# RadToF.net
KiCad netlist of a schematic drawn in Altium Designer
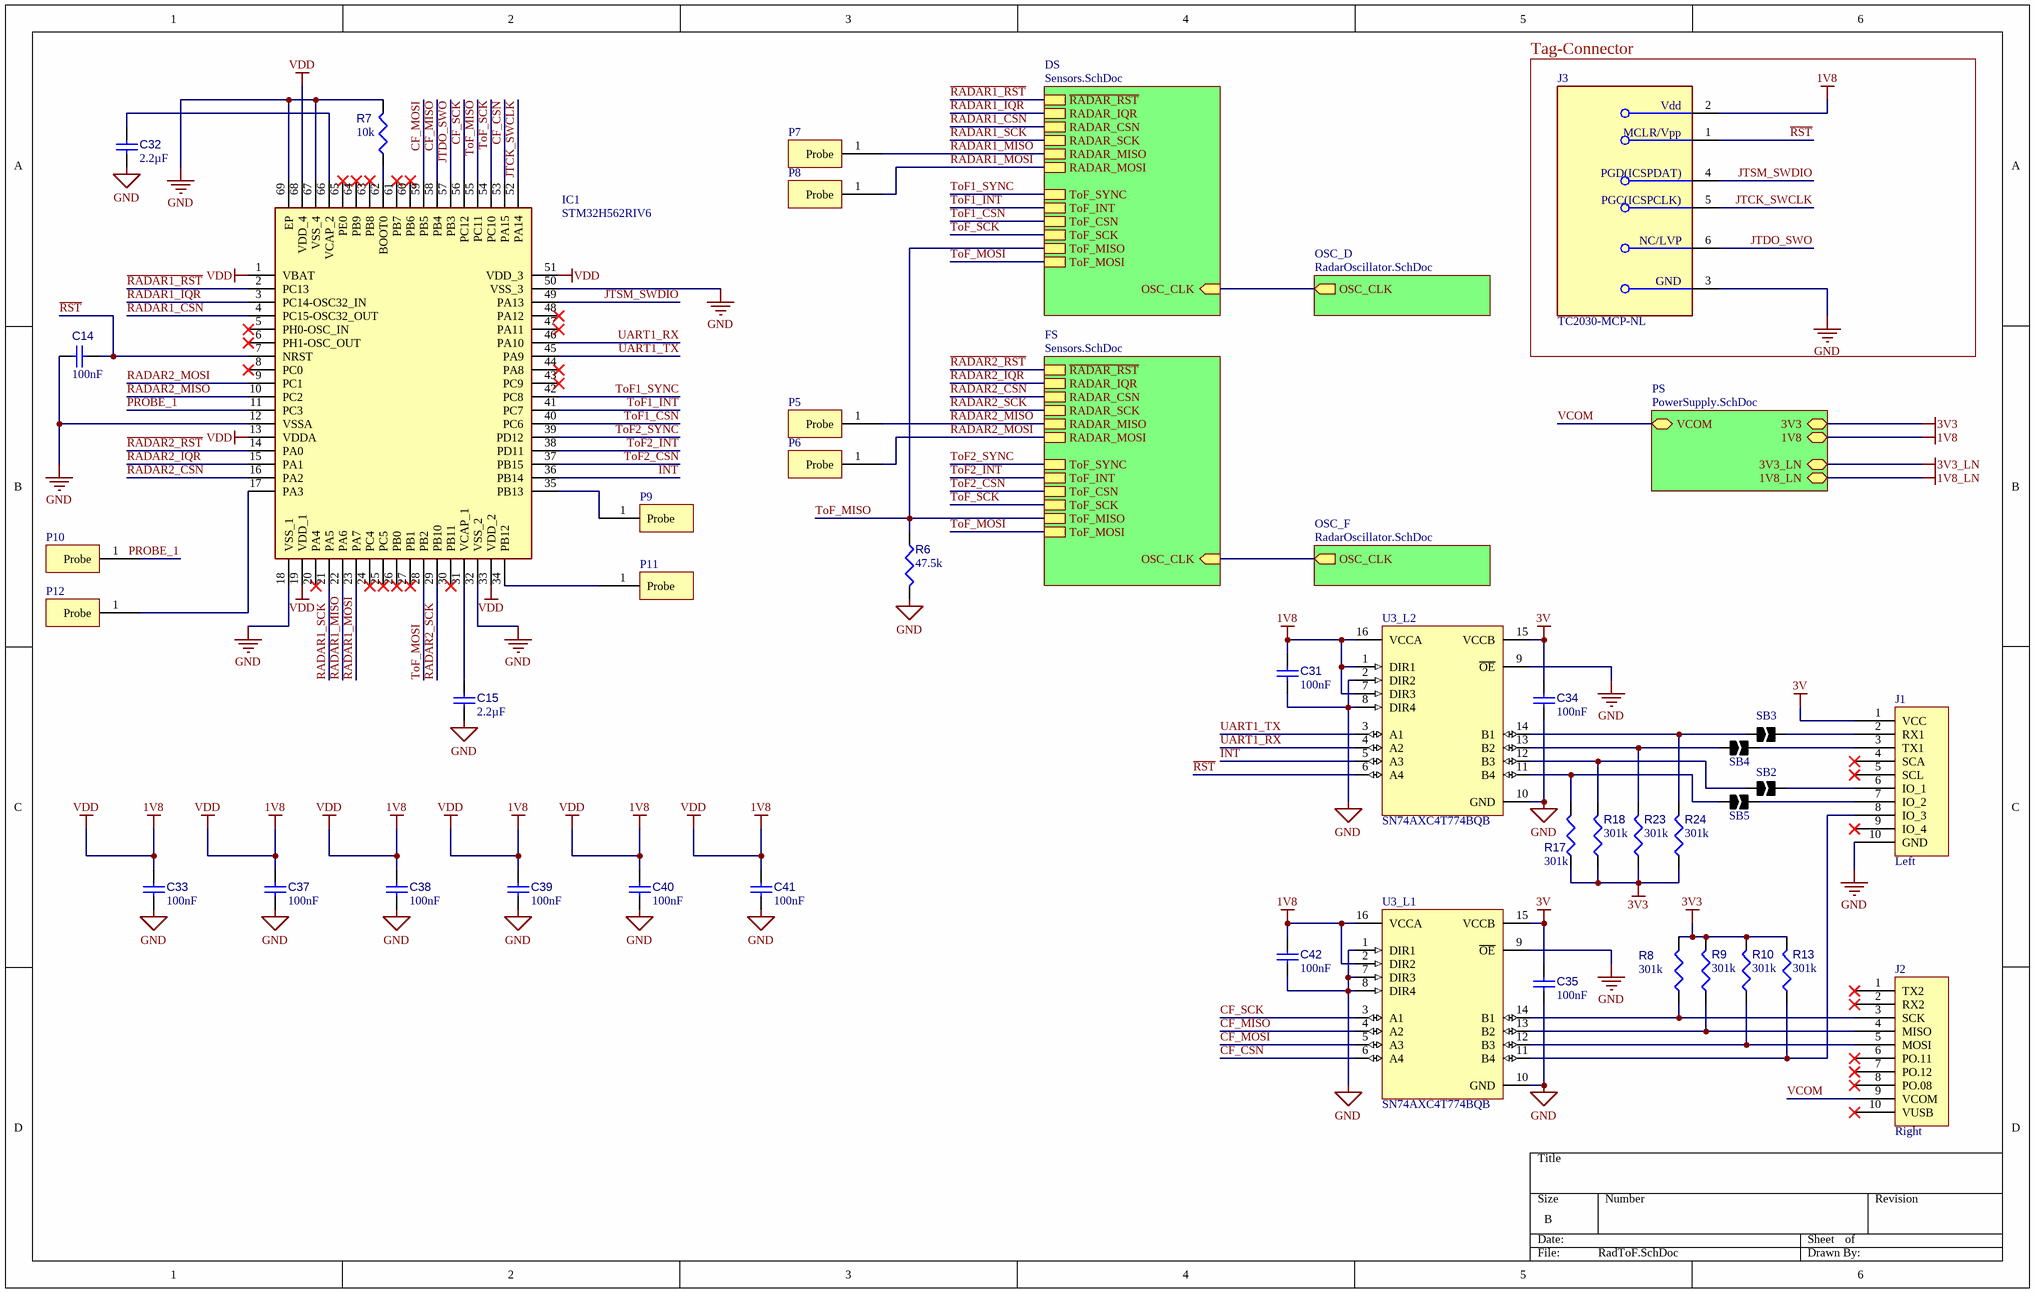
[diagram p0: RadToF.SchDoc]

(export (version "E")
  (design (tool "Eeschema 10.0.6"))
  (components
    (comp (ref "C14")
      (value "100nF")
      (footprint "CAPC0402(1005)60_L")
      (description "Chip Capacitor, 100nF +/-20%, 50V, 0402, Thickness 0.6 mm")
      (fields (field (name "TOLERANCE") "10%") (field (name "Comment") "Capacitor 100nF +/-20% 50V 0402"))
      (libsource (lib "Patrick Hupertz") (part "CAP-NP-2"))
    )
    (comp (ref "C15")
      (value "2.2µF")
      (footprint "CAPC0402(1005)60_L")
      (description "Chip Capacitor, 2,2µF +/-20%, 10V, 0402, Thickness 0.6 mm")
      (fields (field (name "TOLERANCE") "10%") (field (name "Comment") "Capacitor 2,2µF +/-20% 10V 0402"))
      (libsource (lib "Patrick Hupertz") (part "CAP-NP-2"))
    )
    (comp (ref "C31")
      (value "100nF")
      (footprint "CAPC0402(1005)60_L")
      (description "Chip Capacitor, 100nF +/-20%, 50V, 0402, Thickness 0.6 mm")
      (fields (field (name "TOLERANCE") "10%") (field (name "Comment") "Capacitor 100nF +/-20% 50V 0402"))
      (libsource (lib "Patrick Hupertz") (part "CAP-NP-2"))
    )
    (comp (ref "C32")
      (value "2.2µF")
      (footprint "CAPC0402(1005)60_L")
      (description "Chip Capacitor, 2,2µF +/-20%, 10V, 0402, Thickness 0.6 mm")
      (fields (field (name "TOLERANCE") "10%") (field (name "Comment") "Capacitor 2,2µF +/-20% 10V 0402"))
      (libsource (lib "Patrick Hupertz") (part "CAP-NP-2"))
    )
    (comp (ref "C33")
      (value "100nF")
      (footprint "CAPC0402(1005)60_L")
      (description "Chip Capacitor, 100nF +/-20%, 50V, 0402, Thickness 0.6 mm")
      (fields (field (name "TOLERANCE") "10%") (field (name "Comment") "Capacitor 100nF +/-20% 50V 0402"))
      (libsource (lib "Patrick Hupertz") (part "CAP-NP-2"))
    )
    (comp (ref "C34")
      (value "100nF")
      (footprint "CAPC0402(1005)60_L")
      (description "Chip Capacitor, 100nF +/-20%, 50V, 0402, Thickness 0.6 mm")
      (fields (field (name "TOLERANCE") "10%") (field (name "Comment") "Capacitor 100nF +/-20% 50V 0402"))
      (libsource (lib "Patrick Hupertz") (part "CAP-NP-2"))
    )
    (comp (ref "C35")
      (value "100nF")
      (footprint "CAPC0402(1005)60_L")
      (description "Chip Capacitor, 100nF +/-20%, 50V, 0402, Thickness 0.6 mm")
      (fields (field (name "TOLERANCE") "10%") (field (name "Comment") "Capacitor 100nF +/-20% 50V 0402"))
      (libsource (lib "Patrick Hupertz") (part "CAP-NP-2"))
    )
    (comp (ref "C37")
      (value "100nF")
      (footprint "CAPC0402(1005)60_L")
      (description "Chip Capacitor, 100nF +/-20%, 50V, 0402, Thickness 0.6 mm")
      (fields (field (name "TOLERANCE") "10%") (field (name "Comment") "Capacitor 100nF +/-20% 50V 0402"))
      (libsource (lib "Patrick Hupertz") (part "CAP-NP-2"))
    )
    (comp (ref "C38")
      (value "100nF")
      (footprint "CAPC0402(1005)60_L")
      (description "Chip Capacitor, 100nF +/-20%, 50V, 0402, Thickness 0.6 mm")
      (fields (field (name "TOLERANCE") "10%") (field (name "Comment") "Capacitor 100nF +/-20% 50V 0402"))
      (libsource (lib "Patrick Hupertz") (part "CAP-NP-2"))
    )
    (comp (ref "C39")
      (value "100nF")
      (footprint "CAPC0402(1005)60_L")
      (description "Chip Capacitor, 100nF +/-20%, 50V, 0402, Thickness 0.6 mm")
      (fields (field (name "TOLERANCE") "10%") (field (name "Comment") "Capacitor 100nF +/-20% 50V 0402"))
      (libsource (lib "Patrick Hupertz") (part "CAP-NP-2"))
    )
    (comp (ref "C40")
      (value "100nF")
      (footprint "CAPC0402(1005)60_L")
      (description "Chip Capacitor, 100nF +/-20%, 50V, 0402, Thickness 0.6 mm")
      (fields (field (name "TOLERANCE") "10%") (field (name "Comment") "Capacitor 100nF +/-20% 50V 0402"))
      (libsource (lib "Patrick Hupertz") (part "CAP-NP-2"))
    )
    (comp (ref "C41")
      (value "100nF")
      (footprint "CAPC0402(1005)60_L")
      (description "Chip Capacitor, 100nF +/-20%, 50V, 0402, Thickness 0.6 mm")
      (fields (field (name "TOLERANCE") "10%") (field (name "Comment") "Capacitor 100nF +/-20% 50V 0402"))
      (libsource (lib "Patrick Hupertz") (part "CAP-NP-2"))
    )
    (comp (ref "C42")
      (value "100nF")
      (footprint "CAPC0402(1005)60_L")
      (description "Chip Capacitor, 100nF +/-20%, 50V, 0402, Thickness 0.6 mm")
      (fields (field (name "TOLERANCE") "10%") (field (name "Comment") "Capacitor 100nF +/-20% 50V 0402"))
      (libsource (lib "Patrick Hupertz") (part "CAP-NP-2"))
    )
    (comp (ref "IC1")
      (value "STM32H562RIV6")
      (footprint "STM32H562RIV6")
      (fields (field (name "MOUSER PART NUMBER") "511-STM32H562RIV6"))
      (libsource (lib "SchlibPH") (part "STM32H562RIV6"))
    )
    (comp (ref "J1")
      (value "Left")
      (footprint "pcblibPH:CrazyFlieConnector")
      (description "Header to connect to crazy flie pins")
      (libsource (lib "SchlibPH") (part "CrazyFlieHeader_left"))
    )
    (comp (ref "J2")
      (value "Right")
      (footprint "pcblibPH:CrazyFlieConnector")
      (description "Header to connect to crazy flie pins")
      (libsource (lib "SchlibPH") (part "CrazyFlieHeader_right"))
    )
    (comp (ref "J3")
      (value "TC2030-MCP-NL")
      (footprint "FP-TC2030-MCP-NL-MFG")
      (description "CABLE TAG-CONNECT IN-CIRCUIT")
      (libsource (lib "SchlibPH") (part "CMP-205963-000002-1"))
    )
    (comp (ref "P5") (value "~") (footprint "test pad") (libsource (lib "SchlibPH") (part "Test Pad")))
    (comp (ref "P6") (value "~") (footprint "test pad") (libsource (lib "SchlibPH") (part "Test Pad")))
    (comp (ref "P7") (value "~") (footprint "test pad") (libsource (lib "SchlibPH") (part "Test Pad")))
    (comp (ref "P8") (value "~") (footprint "test pad") (libsource (lib "SchlibPH") (part "Test Pad")))
    (comp (ref "P9") (value "~") (footprint "test pad") (libsource (lib "") (part "Test Pad_1")))
    (comp (ref "P10") (value "~") (footprint "test pad") (libsource (lib "SchlibPH") (part "Test Pad")))
    (comp (ref "P11") (value "~") (footprint "test pad") (libsource (lib "") (part "Test Pad_1")))
    (comp (ref "P12") (value "~") (footprint "test pad") (libsource (lib "SchlibPH") (part "Test Pad")))
    (comp (ref "R6")
      (value "47.5k")
      (footprint "RESC0402(1005)_L")
      (description "Chip Resistor, 47,5 kOhms, +/-1 %, 63 mW, -55 to 155 degC, 0402")
      (fields (field (name "POWER") "63mW") (field (name "TOLERANCE") "1%"))
      (libsource (lib "Patrick Hupertz") (part "RES-2"))
    )
    (comp (ref "R7")
      (value "10k")
      (footprint "RESC0402(1005)_L")
      (description "Chip Resistor, 10 kOhms, +/-1 %, 63 mW, -55 to 125 degC, 0402")
      (fields (field (name "POWER") "63mW") (field (name "TOLERANCE") "1%"))
      (libsource (lib "Patrick Hupertz") (part "RES-2"))
    )
    (comp (ref "R8")
      (value "301k")
      (footprint "RESC0402(1005)_L")
      (description "301K 0.063W 1% 0402 (1005 Metric)  SMD")
      (fields (field (name "TOLERANCE") "1%") (field (name "POWER") "63mW"))
      (libsource (lib "Patrick Hupertz") (part "301KR2F"))
    )
    (comp (ref "R9")
      (value "301k")
      (footprint "RESC0402(1005)_L")
      (description "301K 0.063W 1% 0402 (1005 Metric)  SMD")
      (fields (field (name "TOLERANCE") "1%") (field (name "POWER") "63mW"))
      (libsource (lib "Patrick Hupertz") (part "301KR2F"))
    )
    (comp (ref "R10")
      (value "301k")
      (footprint "RESC0402(1005)_L")
      (description "301K 0.063W 1% 0402 (1005 Metric)  SMD")
      (fields (field (name "TOLERANCE") "1%") (field (name "POWER") "63mW"))
      (libsource (lib "Patrick Hupertz") (part "301KR2F"))
    )
    (comp (ref "R13")
      (value "301k")
      (footprint "RESC0402(1005)_L")
      (description "301K 0.063W 1% 0402 (1005 Metric)  SMD")
      (fields (field (name "TOLERANCE") "1%") (field (name "POWER") "63mW"))
      (libsource (lib "Patrick Hupertz") (part "301KR2F"))
    )
    (comp (ref "R17")
      (value "301k")
      (footprint "RESC0402(1005)_L")
      (description "301K 0.063W 1% 0402 (1005 Metric)  SMD")
      (fields (field (name "TOLERANCE") "1%") (field (name "POWER") "63mW"))
      (libsource (lib "Patrick Hupertz") (part "301KR2F"))
    )
    (comp (ref "R18")
      (value "301k")
      (footprint "RESC0402(1005)_L")
      (description "301K 0.063W 1% 0402 (1005 Metric)  SMD")
      (fields (field (name "TOLERANCE") "1%") (field (name "POWER") "63mW"))
      (libsource (lib "Patrick Hupertz") (part "301KR2F"))
    )
    (comp (ref "R23")
      (value "301k")
      (footprint "RESC0402(1005)_L")
      (description "301K 0.063W 1% 0402 (1005 Metric)  SMD")
      (fields (field (name "TOLERANCE") "1%") (field (name "POWER") "63mW"))
      (libsource (lib "Patrick Hupertz") (part "301KR2F"))
    )
    (comp (ref "R24")
      (value "301k")
      (footprint "RESC0402(1005)_L")
      (description "301K 0.063W 1% 0402 (1005 Metric)  SMD")
      (fields (field (name "TOLERANCE") "1%") (field (name "POWER") "63mW"))
      (libsource (lib "Patrick Hupertz") (part "301KR2F"))
    )
    (comp (ref "SB2")
      (value "SB2_0402")
      (footprint "SB2_0402")
      (description "Custom Solder jumper, open")
      (libsource (lib "SchlibPH") (part "JUMP_SB2_0402"))
    )
    (comp (ref "SB3")
      (value "SB2_0402")
      (footprint "SB2_0402")
      (description "Custom Solder jumper, open")
      (libsource (lib "SchlibPH") (part "JUMP_SB2_0402"))
    )
    (comp (ref "SB4")
      (value "SB2_0402")
      (footprint "SB2_0402")
      (description "Custom Solder jumper, open")
      (libsource (lib "SchlibPH") (part "JUMP_SB2_0402"))
    )
    (comp (ref "SB5")
      (value "SB2_0402")
      (footprint "SB2_0402")
      (description "Custom Solder jumper, open")
      (libsource (lib "SchlibPH") (part "JUMP_SB2_0402"))
    )
    (comp (ref "U3_L1")
      (value "SN74AXC4T774BQB")
      (footprint "BQB0016A")
      (fields
        (field (name "MANUFACTURER") "Texas Instruments")
        (field (name "MANUFACTURER PART NUMBER") "SN74AXC4T774BQBR")
      )
      (libsource (lib "SchlibPH") (part "SHIFT_SN74AXC4T774BQB"))
    )
    (comp (ref "U3_L2")
      (value "SN74AXC4T774BQB")
      (footprint "BQB0016A")
      (fields
        (field (name "MANUFACTURER") "Texas Instruments")
        (field (name "MANUFACTURER PART NUMBER") "SN74AXC4T774BQBR")
      )
      (libsource (lib "SchlibPH") (part "SHIFT_SN74AXC4T774BQB"))
    )
  )
  (nets
    (net (code "1") (name "/CF_CSN") (class "Default")
      (node (ref "IC1") (pin "53") (pinfunction "PA15_53") (pintype "passive"))
      (node (ref "U3_L1") (pin "6") (pinfunction "A4_6") (pintype "bidirectional"))
    )
    (net (code "2") (name "/CF_MISO") (class "Default")
      (node (ref "IC1") (pin "58") (pinfunction "PB4_58") (pintype "passive"))
      (node (ref "U3_L1") (pin "4") (pinfunction "A2_4") (pintype "bidirectional"))
    )
    (net (code "3") (name "/CF_MOSI") (class "Default")
      (node (ref "IC1") (pin "59") (pinfunction "PB5_59") (pintype "passive"))
      (node (ref "U3_L1") (pin "5") (pinfunction "A3_5") (pintype "bidirectional"))
    )
    (net (code "4") (name "/CF_SCK") (class "Default")
      (node (ref "IC1") (pin "56") (pinfunction "PC12_56") (pintype "passive"))
      (node (ref "U3_L1") (pin "3") (pinfunction "A1_3") (pintype "bidirectional"))
    )
    (net (code "5") (name "/INT") (class "Default")
      (node (ref "IC1") (pin "36") (pinfunction "PB14_36") (pintype "passive"))
      (node (ref "U3_L2") (pin "5") (pinfunction "A3_5") (pintype "bidirectional"))
    )
    (net (code "6") (name "/JTCK_SWCLK") (class "Default")
      (node (ref "IC1") (pin "52") (pinfunction "PA14_52") (pintype "passive"))
      (node (ref "J3") (pin "5") (pinfunction "PGC(ICSPCLK)_5") (pintype "passive"))
    )
    (net (code "7") (name "/JTDO_SWO") (class "Default")
      (node (ref "IC1") (pin "57") (pinfunction "PB3_57") (pintype "passive"))
      (node (ref "J3") (pin "6") (pinfunction "NC/LVP_6") (pintype "passive"))
    )
    (net (code "8") (name "/JTSM_SWDIO") (class "Default")
      (node (ref "IC1") (pin "49") (pinfunction "PA13_49") (pintype "passive"))
      (node (ref "J3") (pin "4") (pinfunction "PGD(ICSPDAT)_4") (pintype "passive"))
    )
    (net (code "11") (name "/PROBE_1") (class "Default")
      (node (ref "IC1") (pin "11") (pinfunction "PC3_11") (pintype "passive"))
      (node (ref "P10") (pin "1") (pinfunction "Probe_1") (pintype "passive"))
    )
    (net (code "12") (name "/RADAR1_CSN") (class "Default")
      (node (ref "IC1") (pin "4") (pinfunction "PC15-OSC32_OUT_4") (pintype "passive"))
    )
    (net (code "13") (name "/RADAR1_IQR") (class "Default")
      (node (ref "IC1") (pin "3") (pinfunction "PC14-OSC32_IN_3") (pintype "passive"))
    )
    (net (code "14") (name "/RADAR1_MISO") (class "Default")
      (node (ref "IC1") (pin "22") (pinfunction "PA6_22") (pintype "passive"))
      (node (ref "P7") (pin "1") (pinfunction "Probe_1") (pintype "passive"))
    )
    (net (code "15") (name "/RADAR1_MOSI") (class "Default")
      (node (ref "IC1") (pin "23") (pinfunction "PA7_23") (pintype "passive"))
      (node (ref "P8") (pin "1") (pinfunction "Probe_1") (pintype "passive"))
    )
    (net (code "16") (name "/RADAR1_SCK") (class "Default")
      (node (ref "IC1") (pin "21") (pinfunction "PA5_21") (pintype "passive"))
    )
    (net (code "17") (name "/RADAR2_CSN") (class "Default")
      (node (ref "IC1") (pin "16") (pinfunction "PA2_16") (pintype "passive"))
    )
    (net (code "18") (name "/RADAR2_IQR") (class "Default")
      (node (ref "IC1") (pin "15") (pinfunction "PA1_15") (pintype "passive"))
    )
    (net (code "19") (name "/RADAR2_MISO") (class "Default")
      (node (ref "IC1") (pin "10") (pinfunction "PC2_10") (pintype "passive"))
      (node (ref "P5") (pin "1") (pinfunction "Probe_1") (pintype "passive"))
    )
    (net (code "20") (name "/RADAR2_MOSI") (class "Default")
      (node (ref "IC1") (pin "9") (pinfunction "PC1_9") (pintype "passive"))
      (node (ref "P6") (pin "1") (pinfunction "Probe_1") (pintype "passive"))
    )
    (net (code "21") (name "/RADAR2_SCK") (class "Default")
      (node (ref "IC1") (pin "29") (pinfunction "PB10_29") (pintype "passive"))
    )
    (net (code "22") (name "/ToF1_CSN") (class "Default")
      (node (ref "IC1") (pin "40") (pinfunction "PC6_40") (pintype "passive"))
    )
    (net (code "23") (name "/ToF1_INT") (class "Default")
      (node (ref "IC1") (pin "41") (pinfunction "PC7_41") (pintype "passive"))
    )
    (net (code "24") (name "/ToF1_SYNC") (class "Default")
      (node (ref "IC1") (pin "42") (pinfunction "PC8_42") (pintype "passive"))
    )
    (net (code "25") (name "/ToF2_CSN") (class "Default")
      (node (ref "IC1") (pin "37") (pinfunction "PB15_37") (pintype "passive"))
    )
    (net (code "26") (name "/ToF2_INT") (class "Default")
      (node (ref "IC1") (pin "38") (pinfunction "PD11_38") (pintype "passive"))
    )
    (net (code "27") (name "/ToF2_SYNC") (class "Default")
      (node (ref "IC1") (pin "39") (pinfunction "PD12_39") (pintype "passive"))
    )
    (net (code "28") (name "/ToF_MISO") (class "Default")
      (node (ref "IC1") (pin "55") (pinfunction "PC11_55") (pintype "passive"))
      (node (ref "R6") (pin "1") (pinfunction "1_1") (pintype "passive"))
    )
    (net (code "29") (name "/ToF_MOSI") (class "Default")
      (node (ref "IC1") (pin "28") (pinfunction "PB2_28") (pintype "passive"))
    )
    (net (code "30") (name "/ToF_SCK") (class "Default")
      (node (ref "IC1") (pin "54") (pinfunction "PC10_54") (pintype "passive"))
    )
    (net (code "31") (name "/UART1_RX") (class "Default")
      (node (ref "IC1") (pin "46") (pinfunction "PA10_46") (pintype "passive"))
      (node (ref "U3_L2") (pin "4") (pinfunction "A2_4") (pintype "bidirectional"))
    )
    (net (code "32") (name "/UART1_TX") (class "Default")
      (node (ref "IC1") (pin "45") (pinfunction "PA9_45") (pintype "passive"))
      (node (ref "U3_L2") (pin "3") (pinfunction "A1_3") (pintype "bidirectional"))
    )
    (net (code "33") (name "/VCOM") (class "Default")
      (node (ref "J2") (pin "9") (pinfunction "VCOM_9") (pintype "passive"))
    )
    (net (code "34") (name "/~{RADAR1_RST}") (class "Default")
      (node (ref "IC1") (pin "2") (pinfunction "PC13_2") (pintype "passive"))
    )
    (net (code "35") (name "/~{RADAR2_RST}") (class "Default")
      (node (ref "IC1") (pin "14") (pinfunction "PA0_14") (pintype "passive"))
    )
    (net (code "36") (name "/~{RST}") (class "Default")
      (node (ref "C14") (pin "1") (pinfunction "1_1") (pintype "passive"))
      (node (ref "IC1") (pin "7") (pinfunction "NRST_7") (pintype "passive"))
      (node (ref "J3") (pin "1") (pinfunction "MCLR/Vpp_1") (pintype "passive"))
      (node (ref "U3_L2") (pin "6") (pinfunction "A4_6") (pintype "bidirectional"))
    )
    (net (code "37") (name "1V8") (class "Default")
      (node (ref "C31") (pin "1") (pinfunction "1_1") (pintype "passive"))
      (node (ref "C33") (pin "2") (pinfunction "2_2") (pintype "passive"))
      (node (ref "C37") (pin "2") (pinfunction "2_2") (pintype "passive"))
      (node (ref "C38") (pin "2") (pinfunction "2_2") (pintype "passive"))
      (node (ref "C39") (pin "2") (pinfunction "2_2") (pintype "passive"))
      (node (ref "C40") (pin "2") (pinfunction "2_2") (pintype "passive"))
      (node (ref "C41") (pin "2") (pinfunction "2_2") (pintype "passive"))
      (node (ref "C42") (pin "1") (pinfunction "1_1") (pintype "passive"))
      (node (ref "IC1") (pin "1") (pinfunction "VBAT_1") (pintype "passive"))
      (node (ref "IC1") (pin "13") (pinfunction "VDDA_13") (pintype "passive"))
      (node (ref "IC1") (pin "19") (pinfunction "VDD_1_19") (pintype "passive"))
      (node (ref "IC1") (pin "33") (pinfunction "VDD_2_33") (pintype "passive"))
      (node (ref "IC1") (pin "51") (pinfunction "VDD_3_51") (pintype "passive"))
      (node (ref "IC1") (pin "68") (pinfunction "VDD_4_68") (pintype "passive"))
      (node (ref "J3") (pin "2") (pinfunction "Vdd_2") (pintype "passive"))
      (node (ref "U3_L1") (pin "16") (pinfunction "VCCA_16") (pintype "power_in"))
      (node (ref "U3_L1") (pin "2") (pinfunction "DIR2_2") (pintype "input"))
      (node (ref "U3_L2") (pin "1") (pinfunction "DIR1_1") (pintype "input"))
      (node (ref "U3_L2") (pin "16") (pinfunction "VCCA_16") (pintype "power_in"))
      (node (ref "U3_L2") (pin "7") (pinfunction "DIR3_7") (pintype "input"))
    )
    (net (code "39") (name "3V") (class "Default")
      (node (ref "C34") (pin "1") (pinfunction "1_1") (pintype "passive"))
      (node (ref "C35") (pin "1") (pinfunction "1_1") (pintype "passive"))
      (node (ref "J1") (pin "1") (pinfunction "VCC_1") (pintype "passive"))
      (node (ref "U3_L1") (pin "15") (pinfunction "VCCB_15") (pintype "power_in"))
      (node (ref "U3_L2") (pin "15") (pinfunction "VCCB_15") (pintype "power_in"))
    )
    (net (code "40") (name "3V3") (class "Default")
      (node (ref "R10") (pin "2") (pinfunction "2_2") (pintype "passive"))
      (node (ref "R13") (pin "2") (pinfunction "2_2") (pintype "passive"))
      (node (ref "R17") (pin "1") (pinfunction "1_1") (pintype "passive"))
      (node (ref "R18") (pin "1") (pinfunction "1_1") (pintype "passive"))
      (node (ref "R23") (pin "1") (pinfunction "1_1") (pintype "passive"))
      (node (ref "R24") (pin "1") (pinfunction "1_1") (pintype "passive"))
      (node (ref "R8") (pin "2") (pinfunction "2_2") (pintype "passive"))
      (node (ref "R9") (pin "2") (pinfunction "2_2") (pintype "passive"))
    )
    (net (code "42") (name "GND") (class "Default")
      (node (ref "C14") (pin "2") (pinfunction "2_2") (pintype "passive"))
      (node (ref "C15") (pin "1") (pinfunction "1_1") (pintype "passive"))
      (node (ref "C31") (pin "2") (pinfunction "2_2") (pintype "passive"))
      (node (ref "C32") (pin "1") (pinfunction "1_1") (pintype "passive"))
      (node (ref "C33") (pin "1") (pinfunction "1_1") (pintype "passive"))
      (node (ref "C34") (pin "2") (pinfunction "2_2") (pintype "passive"))
      (node (ref "C35") (pin "2") (pinfunction "2_2") (pintype "passive"))
      (node (ref "C37") (pin "1") (pinfunction "1_1") (pintype "passive"))
      (node (ref "C38") (pin "1") (pinfunction "1_1") (pintype "passive"))
      (node (ref "C39") (pin "1") (pinfunction "1_1") (pintype "passive"))
      (node (ref "C40") (pin "1") (pinfunction "1_1") (pintype "passive"))
      (node (ref "C41") (pin "1") (pinfunction "1_1") (pintype "passive"))
      (node (ref "C42") (pin "2") (pinfunction "2_2") (pintype "passive"))
      (node (ref "IC1") (pin "12") (pinfunction "VSSA_12") (pintype "passive"))
      (node (ref "IC1") (pin "18") (pinfunction "VSS_1_18") (pintype "passive"))
      (node (ref "IC1") (pin "32") (pinfunction "VSS_2_32") (pintype "passive"))
      (node (ref "IC1") (pin "50") (pinfunction "VSS_3_50") (pintype "passive"))
      (node (ref "IC1") (pin "67") (pinfunction "VSS_4_67") (pintype "passive"))
      (node (ref "IC1") (pin "69") (pinfunction "EP_69") (pintype "passive"))
      (node (ref "J1") (pin "10") (pinfunction "GND_10") (pintype "passive"))
      (node (ref "J3") (pin "3") (pinfunction "GND_3") (pintype "passive"))
      (node (ref "R6") (pin "2") (pinfunction "2_2") (pintype "passive"))
      (node (ref "R7") (pin "2") (pinfunction "2_2") (pintype "passive"))
      (node (ref "U3_L1") (pin "1") (pinfunction "DIR1_1") (pintype "input"))
      (node (ref "U3_L1") (pin "10") (pinfunction "GND_10") (pintype "power_in"))
      (node (ref "U3_L1") (pin "7") (pinfunction "DIR3_7") (pintype "input"))
      (node (ref "U3_L1") (pin "8") (pinfunction "DIR4_8") (pintype "input"))
      (node (ref "U3_L1") (pin "9") (pinfunction "~{OE}_9") (pintype "passive"))
      (node (ref "U3_L2") (pin "10") (pinfunction "GND_10") (pintype "power_in"))
      (node (ref "U3_L2") (pin "2") (pinfunction "DIR2_2") (pintype "input"))
      (node (ref "U3_L2") (pin "8") (pinfunction "DIR4_8") (pintype "input"))
      (node (ref "U3_L2") (pin "9") (pinfunction "~{OE}_9") (pintype "passive"))
    )
    (net (code "43") (name "Net-(IC1-BOOT0)") (class "Default")
      (node (ref "IC1") (pin "62") (pinfunction "BOOT0_62") (pintype "passive"))
      (node (ref "R7") (pin "1") (pinfunction "1_1") (pintype "passive"))
    )
    (net (code "44") (name "Net-(IC1-PA3)") (class "Default")
      (node (ref "IC1") (pin "17") (pinfunction "PA3_17") (pintype "passive"))
      (node (ref "P12") (pin "1") (pinfunction "Probe_1") (pintype "passive"))
    )
    (net (code "45") (name "Net-(IC1-PB12)") (class "Default")
      (node (ref "IC1") (pin "34") (pinfunction "PB12_34") (pintype "passive"))
      (node (ref "P11") (pin "1") (pinfunction "Probe_1") (pintype "passive"))
    )
    (net (code "46") (name "Net-(IC1-PB13)") (class "Default")
      (node (ref "IC1") (pin "35") (pinfunction "PB13_35") (pintype "passive"))
      (node (ref "P9") (pin "1") (pinfunction "Probe_1") (pintype "passive"))
    )
    (net (code "47") (name "Net-(IC1-VCAP_1)") (class "Default")
      (node (ref "C15") (pin "2") (pinfunction "2_2") (pintype "passive"))
      (node (ref "IC1") (pin "31") (pinfunction "VCAP_1_31") (pintype "passive"))
    )
    (net (code "48") (name "Net-(IC1-VCAP_2)") (class "Default")
      (node (ref "C32") (pin "2") (pinfunction "2_2") (pintype "passive"))
      (node (ref "IC1") (pin "66") (pinfunction "VCAP_2_66") (pintype "passive"))
    )
    (net (code "49") (name "Net-(J1-IO_1)") (class "Default")
      (node (ref "J1") (pin "6") (pinfunction "IO_1_6") (pintype "passive"))
      (node (ref "SB2") (pin "1") (pinfunction "1_1") (pintype "passive"))
    )
    (net (code "50") (name "Net-(J1-IO_2)") (class "Default")
      (node (ref "J1") (pin "7") (pinfunction "IO_2_7") (pintype "passive"))
      (node (ref "SB5") (pin "1") (pinfunction "1_1") (pintype "passive"))
    )
    (net (code "51") (name "Net-(J1-IO_3)") (class "Default")
      (node (ref "J1") (pin "8") (pinfunction "IO_3_8") (pintype "passive"))
      (node (ref "R13") (pin "1") (pinfunction "1_1") (pintype "passive"))
      (node (ref "U3_L1") (pin "11") (pinfunction "B4_11") (pintype "bidirectional"))
    )
    (net (code "52") (name "Net-(J1-RX1)") (class "Default")
      (node (ref "J1") (pin "2") (pinfunction "RX1_2") (pintype "passive"))
      (node (ref "SB3") (pin "1") (pinfunction "1_1") (pintype "passive"))
    )
    (net (code "53") (name "Net-(J1-TX1)") (class "Default")
      (node (ref "J1") (pin "3") (pinfunction "TX1_3") (pintype "passive"))
      (node (ref "SB4") (pin "1") (pinfunction "1_1") (pintype "passive"))
    )
    (net (code "54") (name "Net-(J2-MISO)") (class "Default")
      (node (ref "J2") (pin "4") (pinfunction "MISO_4") (pintype "passive"))
      (node (ref "R9") (pin "1") (pinfunction "1_1") (pintype "passive"))
      (node (ref "U3_L1") (pin "13") (pinfunction "B2_13") (pintype "bidirectional"))
    )
    (net (code "55") (name "Net-(J2-MOSI)") (class "Default")
      (node (ref "J2") (pin "5") (pinfunction "MOSI_5") (pintype "passive"))
      (node (ref "R10") (pin "1") (pinfunction "1_1") (pintype "passive"))
      (node (ref "U3_L1") (pin "12") (pinfunction "B3_12") (pintype "bidirectional"))
    )
    (net (code "56") (name "Net-(J2-SCK)") (class "Default")
      (node (ref "J2") (pin "3") (pinfunction "SCK_3") (pintype "passive"))
      (node (ref "R8") (pin "1") (pinfunction "1_1") (pintype "passive"))
      (node (ref "U3_L1") (pin "14") (pinfunction "B1_14") (pintype "bidirectional"))
    )
    (net (code "57") (name "Net-(U3_L2-B1)") (class "Default")
      (node (ref "R24") (pin "2") (pinfunction "2_2") (pintype "passive"))
      (node (ref "SB3") (pin "2") (pinfunction "2_2") (pintype "passive"))
      (node (ref "U3_L2") (pin "14") (pinfunction "B1_14") (pintype "bidirectional"))
    )
    (net (code "58") (name "Net-(U3_L2-B2)") (class "Default")
      (node (ref "R23") (pin "2") (pinfunction "2_2") (pintype "passive"))
      (node (ref "SB4") (pin "2") (pinfunction "2_2") (pintype "passive"))
      (node (ref "U3_L2") (pin "13") (pinfunction "B2_13") (pintype "bidirectional"))
    )
    (net (code "59") (name "Net-(U3_L2-B3)") (class "Default")
      (node (ref "R18") (pin "2") (pinfunction "2_2") (pintype "passive"))
      (node (ref "SB2") (pin "2") (pinfunction "2_2") (pintype "passive"))
      (node (ref "U3_L2") (pin "12") (pinfunction "B3_12") (pintype "bidirectional"))
    )
    (net (code "60") (name "Net-(U3_L2-B4)") (class "Default")
      (node (ref "R17") (pin "2") (pinfunction "2_2") (pintype "passive"))
      (node (ref "SB5") (pin "2") (pinfunction "2_2") (pintype "passive"))
      (node (ref "U3_L2") (pin "11") (pinfunction "B4_11") (pintype "bidirectional"))
    )
    (net (code "61") (name "unconnected-(IC1-PA4-Pad20)") (class "Default")
      (node (ref "IC1") (pin "20") (pinfunction "PA4_20") (pintype "passive+no_connect"))
    )
    (net (code "62") (name "unconnected-(IC1-PA8-Pad44)") (class "Default")
      (node (ref "IC1") (pin "44") (pinfunction "PA8_44") (pintype "passive+no_connect"))
    )
    (net (code "63") (name "unconnected-(IC1-PA11-Pad47)") (class "Default")
      (node (ref "IC1") (pin "47") (pinfunction "PA11_47") (pintype "passive+no_connect"))
    )
    (net (code "64") (name "unconnected-(IC1-PA12-Pad48)") (class "Default")
      (node (ref "IC1") (pin "48") (pinfunction "PA12_48") (pintype "passive+no_connect"))
    )
    (net (code "65") (name "unconnected-(IC1-PB0-Pad26)") (class "Default")
      (node (ref "IC1") (pin "26") (pinfunction "PB0_26") (pintype "passive+no_connect"))
    )
    (net (code "66") (name "unconnected-(IC1-PB1-Pad27)") (class "Default")
      (node (ref "IC1") (pin "27") (pinfunction "PB1_27") (pintype "passive+no_connect"))
    )
    (net (code "67") (name "unconnected-(IC1-PB6-Pad60)") (class "Default")
      (node (ref "IC1") (pin "60") (pinfunction "PB6_60") (pintype "passive+no_connect"))
    )
    (net (code "68") (name "unconnected-(IC1-PB7-Pad61)") (class "Default")
      (node (ref "IC1") (pin "61") (pinfunction "PB7_61") (pintype "passive+no_connect"))
    )
    (net (code "69") (name "unconnected-(IC1-PB8-Pad63)") (class "Default")
      (node (ref "IC1") (pin "63") (pinfunction "PB8_63") (pintype "passive+no_connect"))
    )
    (net (code "70") (name "unconnected-(IC1-PB9-Pad64)") (class "Default")
      (node (ref "IC1") (pin "64") (pinfunction "PB9_64") (pintype "passive+no_connect"))
    )
    (net (code "71") (name "unconnected-(IC1-PB11-Pad30)") (class "Default")
      (node (ref "IC1") (pin "30") (pinfunction "PB11_30") (pintype "passive+no_connect"))
    )
    (net (code "72") (name "unconnected-(IC1-PC0-Pad8)") (class "Default")
      (node (ref "IC1") (pin "8") (pinfunction "PC0_8") (pintype "passive+no_connect"))
    )
    (net (code "73") (name "unconnected-(IC1-PC4-Pad24)") (class "Default")
      (node (ref "IC1") (pin "24") (pinfunction "PC4_24") (pintype "passive+no_connect"))
    )
    (net (code "74") (name "unconnected-(IC1-PC5-Pad25)") (class "Default")
      (node (ref "IC1") (pin "25") (pinfunction "PC5_25") (pintype "passive+no_connect"))
    )
    (net (code "75") (name "unconnected-(IC1-PC9-Pad43)") (class "Default")
      (node (ref "IC1") (pin "43") (pinfunction "PC9_43") (pintype "passive+no_connect"))
    )
    (net (code "76") (name "unconnected-(IC1-PE0-Pad65)") (class "Default")
      (node (ref "IC1") (pin "65") (pinfunction "PE0_65") (pintype "passive+no_connect"))
    )
    (net (code "77") (name "unconnected-(IC1-PH0-OSC_IN-Pad5)") (class "Default")
      (node (ref "IC1") (pin "5") (pinfunction "PH0-OSC_IN_5") (pintype "passive+no_connect"))
    )
    (net (code "78") (name "unconnected-(IC1-PH1-OSC_OUT-Pad6)") (class "Default")
      (node (ref "IC1") (pin "6") (pinfunction "PH1-OSC_OUT_6") (pintype "passive+no_connect"))
    )
    (net (code "79") (name "unconnected-(J1-IO_4-Pad9)") (class "Default")
      (node (ref "J1") (pin "9") (pinfunction "IO_4_9") (pintype "passive+no_connect"))
    )
    (net (code "80") (name "unconnected-(J1-SCA-Pad4)") (class "Default")
      (node (ref "J1") (pin "4") (pinfunction "SCA_4") (pintype "passive+no_connect"))
    )
    (net (code "81") (name "unconnected-(J1-SCL-Pad5)") (class "Default")
      (node (ref "J1") (pin "5") (pinfunction "SCL_5") (pintype "passive+no_connect"))
    )
    (net (code "82") (name "unconnected-(J2-PO.08-Pad8)") (class "Default")
      (node (ref "J2") (pin "8") (pinfunction "PO.08_8") (pintype "passive+no_connect"))
    )
    (net (code "83") (name "unconnected-(J2-PO.11-Pad6)") (class "Default")
      (node (ref "J2") (pin "6") (pinfunction "PO.11_6") (pintype "passive+no_connect"))
    )
    (net (code "84") (name "unconnected-(J2-PO.12-Pad7)") (class "Default")
      (node (ref "J2") (pin "7") (pinfunction "PO.12_7") (pintype "passive+no_connect"))
    )
    (net (code "85") (name "unconnected-(J2-RX2-Pad2)") (class "Default")
      (node (ref "J2") (pin "2") (pinfunction "RX2_2") (pintype "passive+no_connect"))
    )
    (net (code "86") (name "unconnected-(J2-TX2-Pad1)") (class "Default")
      (node (ref "J2") (pin "1") (pinfunction "TX2_1") (pintype "passive+no_connect"))
    )
    (net (code "87") (name "unconnected-(J2-VUSB-Pad10)") (class "Default")
      (node (ref "J2") (pin "10") (pinfunction "VUSB_10") (pintype "power_in+no_connect"))
    )
  )
)
